# v1_0_r2.net
KiCad netlist of a schematic drawn in EAGLE
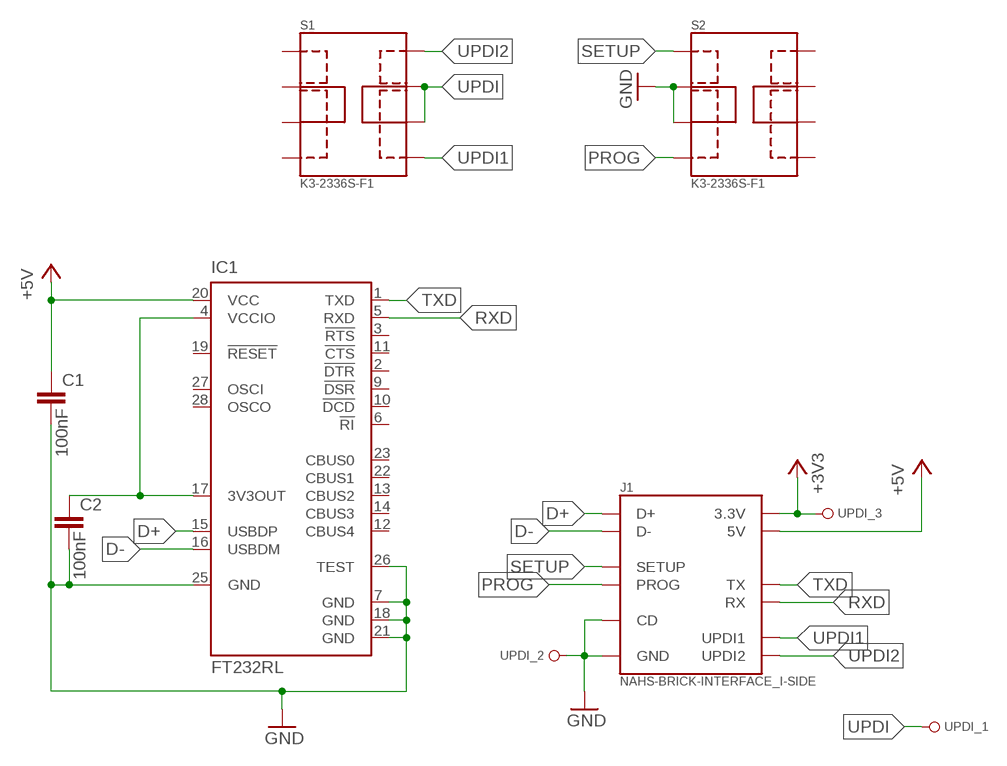
[diagram p0: schematic, sheet 1]

(export (version "E")
  (design (tool "Eeschema 10.0.6"))
  (components
    (comp (ref "C1")
      (value "100nF")
      (footprint "eagle-import:C0805")
      (libsource (lib "eagle-import") (part "C-EUC0805"))
    )
    (comp (ref "C2")
      (value "100nF")
      (footprint "eagle-import:C0805")
      (libsource (lib "eagle-import") (part "C-EUC0805"))
    )
    (comp (ref "IC1")
      (value "FT232RL")
      (footprint "eagle-import:SSOP28")
      (libsource (lib "eagle-import") (part "FT232RL"))
    )
    (comp (ref "J1")
      (value "NAHS-BRICK-INTERFACE_I-SIDE")
      (footprint "eagle-import:54102-0164")
      (libsource (lib "eagle-import") (part "NAHS-BRICK-INTERFACE_I-SIDE"))
    )
    (comp (ref "S1")
      (value "K3-2336S-F1")
      (footprint "eagle-import:K3-2336S-F1")
      (libsource (lib "eagle-import") (part "K3-2336S-F1"))
    )
    (comp (ref "S2")
      (value "K3-2336S-F1")
      (footprint "eagle-import:K3-2336S-F1")
      (libsource (lib "eagle-import") (part "K3-2336S-F1"))
    )
    (comp (ref "UPDI")
      (value "PINHD_1X03_R_1")
      (footprint "eagle-import:1X03_R_1")
      (libsource (lib "eagle-import") (part "PINHD_1X03_R_1"))
    )
  )
  (nets
    (net (code "1") (name "+3V3") (class "Default")
      (node (ref "J1") (pin "16") (pinfunction "3.3V_16") (pintype "bidirectional"))
      (node (ref "UPDI") (pin "3") (pinfunction "1_3") (pintype "bidirectional"))
    )
    (net (code "2") (name "+5V") (class "Default")
      (node (ref "C1") (pin "1") (pinfunction "1_1") (pintype "passive"))
      (node (ref "IC1") (pin "20") (pinfunction "VCC_20") (pintype "power_in"))
      (node (ref "J1") (pin "5") (pinfunction "5V_5") (pintype "bidirectional"))
      (node (ref "J1") (pin "6") (pinfunction "5V_6") (pintype "bidirectional"))
    )
    (net (code "3") (name "D+") (class "Default")
      (node (ref "IC1") (pin "15") (pinfunction "USBDP_15") (pintype "bidirectional"))
      (node (ref "J1") (pin "9") (pinfunction "D+_9") (pintype "bidirectional"))
    )
    (net (code "4") (name "D-") (class "Default")
      (node (ref "IC1") (pin "16") (pinfunction "USBDM_16") (pintype "bidirectional"))
      (node (ref "J1") (pin "10") (pinfunction "D-_10") (pintype "bidirectional"))
    )
    (net (code "5") (name "GND") (class "Default")
      (node (ref "C1") (pin "2") (pinfunction "2_2") (pintype "passive"))
      (node (ref "C2") (pin "2") (pinfunction "2_2") (pintype "passive"))
      (node (ref "IC1") (pin "18") (pinfunction "GND_18") (pintype "power_in"))
      (node (ref "IC1") (pin "21") (pinfunction "GND_21") (pintype "power_in"))
      (node (ref "IC1") (pin "25") (pinfunction "GND_25") (pintype "power_in"))
      (node (ref "IC1") (pin "26") (pinfunction "TEST_26") (pintype "input"))
      (node (ref "IC1") (pin "7") (pinfunction "GND_7") (pintype "power_in"))
      (node (ref "J1") (pin "11") (pinfunction "GND_11") (pintype "bidirectional"))
      (node (ref "J1") (pin "12") (pinfunction "GND_12") (pintype "bidirectional"))
      (node (ref "J1") (pin "13") (pinfunction "CD_13") (pintype "bidirectional"))
      (node (ref "S2") (pin "1.2") (pinfunction "1.2_1.2") (pintype "bidirectional"))
      (node (ref "S2") (pin "1.3") (pinfunction "1.3_1.3") (pintype "bidirectional"))
      (node (ref "UPDI") (pin "2") (pinfunction "1_2") (pintype "bidirectional"))
    )
    (net (code "6") (name "Net-(IC1-3V3OUT)") (class "Default")
      (node (ref "C2") (pin "1") (pinfunction "1_1") (pintype "passive"))
      (node (ref "IC1") (pin "17") (pinfunction "3V3OUT_17") (pintype "output"))
      (node (ref "IC1") (pin "4") (pinfunction "VCCIO_4") (pintype "power_in"))
    )
    (net (code "7") (name "PROG") (class "Default")
      (node (ref "J1") (pin "1") (pinfunction "PROG_1") (pintype "bidirectional"))
      (node (ref "S2") (pin "1.4") (pinfunction "1.4_1.4") (pintype "bidirectional"))
    )
    (net (code "8") (name "RXD") (class "Default")
      (node (ref "IC1") (pin "5") (pinfunction "RXD_5") (pintype "input"))
      (node (ref "J1") (pin "8") (pinfunction "RX_8") (pintype "bidirectional"))
    )
    (net (code "9") (name "SETUP") (class "Default")
      (node (ref "J1") (pin "2") (pinfunction "SETUP_2") (pintype "bidirectional"))
      (node (ref "S2") (pin "1.1") (pinfunction "1.1_1.1") (pintype "bidirectional"))
    )
    (net (code "10") (name "TXD") (class "Default")
      (node (ref "IC1") (pin "1") (pinfunction "TXD_1") (pintype "output"))
      (node (ref "J1") (pin "7") (pinfunction "TX_7") (pintype "bidirectional"))
    )
    (net (code "11") (name "UPDI") (class "Default")
      (node (ref "S1") (pin "2.2") (pinfunction "2.2_2.2") (pintype "bidirectional"))
      (node (ref "S1") (pin "2.3") (pinfunction "2.3_2.3") (pintype "bidirectional"))
      (node (ref "UPDI") (pin "1") (pinfunction "1_1") (pintype "bidirectional"))
    )
    (net (code "12") (name "UPDI1") (class "Default")
      (node (ref "J1") (pin "15") (pinfunction "UPDI1_15") (pintype "bidirectional"))
      (node (ref "S1") (pin "2.4") (pinfunction "2.4_2.4") (pintype "bidirectional"))
    )
    (net (code "13") (name "UPDI2") (class "Default")
      (node (ref "J1") (pin "14") (pinfunction "UPDI2_14") (pintype "bidirectional"))
      (node (ref "S1") (pin "2.1") (pinfunction "2.1_2.1") (pintype "bidirectional"))
    )
    (net (code "14") (name "unconnected-(IC1-CBUS0-Pad23)") (class "Default")
      (node (ref "IC1") (pin "23") (pinfunction "CBUS0_23") (pintype "bidirectional"))
    )
    (net (code "15") (name "unconnected-(IC1-CBUS1-Pad22)") (class "Default")
      (node (ref "IC1") (pin "22") (pinfunction "CBUS1_22") (pintype "bidirectional"))
    )
    (net (code "16") (name "unconnected-(IC1-CBUS2-Pad13)") (class "Default")
      (node (ref "IC1") (pin "13") (pinfunction "CBUS2_13") (pintype "bidirectional"))
    )
    (net (code "17") (name "unconnected-(IC1-CBUS3-Pad14)") (class "Default")
      (node (ref "IC1") (pin "14") (pinfunction "CBUS3_14") (pintype "bidirectional"))
    )
    (net (code "18") (name "unconnected-(IC1-CBUS4-Pad12)") (class "Default")
      (node (ref "IC1") (pin "12") (pinfunction "CBUS4_12") (pintype "bidirectional"))
    )
    (net (code "19") (name "unconnected-(IC1-OSCI-Pad27)") (class "Default")
      (node (ref "IC1") (pin "27") (pinfunction "OSCI_27") (pintype "input"))
    )
    (net (code "20") (name "unconnected-(IC1-OSCO-Pad28)") (class "Default")
      (node (ref "IC1") (pin "28") (pinfunction "OSCO_28") (pintype "output"))
    )
    (net (code "21") (name "unconnected-(IC1-~{CTS}-Pad11)") (class "Default")
      (node (ref "IC1") (pin "11") (pinfunction "~{CTS}_11") (pintype "input"))
    )
    (net (code "22") (name "unconnected-(IC1-~{DCD}-Pad10)") (class "Default")
      (node (ref "IC1") (pin "10") (pinfunction "~{DCD}_10") (pintype "input"))
    )
    (net (code "23") (name "unconnected-(IC1-~{DSR}-Pad9)") (class "Default")
      (node (ref "IC1") (pin "9") (pinfunction "~{DSR}_9") (pintype "input"))
    )
    (net (code "24") (name "unconnected-(IC1-~{DTR}-Pad2)") (class "Default")
      (node (ref "IC1") (pin "2") (pinfunction "~{DTR}_2") (pintype "output"))
    )
    (net (code "25") (name "unconnected-(IC1-~{RESET}-Pad19)") (class "Default")
      (node (ref "IC1") (pin "19") (pinfunction "~{RESET}_19") (pintype "input"))
    )
    (net (code "26") (name "unconnected-(IC1-~{RI}-Pad6)") (class "Default")
      (node (ref "IC1") (pin "6") (pinfunction "~{RI}_6") (pintype "input"))
    )
    (net (code "27") (name "unconnected-(IC1-~{RTS}-Pad3)") (class "Default")
      (node (ref "IC1") (pin "3") (pinfunction "~{RTS}_3") (pintype "output"))
    )
    (net (code "28") (name "unconnected-(S1-Pad1.1)") (class "Default")
      (node (ref "S1") (pin "1.1") (pinfunction "1.1_1.1") (pintype "bidirectional"))
    )
    (net (code "29") (name "unconnected-(S1-Pad1.2)") (class "Default")
      (node (ref "S1") (pin "1.2") (pinfunction "1.2_1.2") (pintype "bidirectional"))
    )
    (net (code "30") (name "unconnected-(S1-Pad1.3)") (class "Default")
      (node (ref "S1") (pin "1.3") (pinfunction "1.3_1.3") (pintype "bidirectional"))
    )
    (net (code "31") (name "unconnected-(S1-Pad1.4)") (class "Default")
      (node (ref "S1") (pin "1.4") (pinfunction "1.4_1.4") (pintype "bidirectional"))
    )
    (net (code "32") (name "unconnected-(S2-Pad2.1)") (class "Default")
      (node (ref "S2") (pin "2.1") (pinfunction "2.1_2.1") (pintype "bidirectional"))
    )
    (net (code "33") (name "unconnected-(S2-Pad2.2)") (class "Default")
      (node (ref "S2") (pin "2.2") (pinfunction "2.2_2.2") (pintype "bidirectional"))
    )
    (net (code "34") (name "unconnected-(S2-Pad2.3)") (class "Default")
      (node (ref "S2") (pin "2.3") (pinfunction "2.3_2.3") (pintype "bidirectional"))
    )
    (net (code "35") (name "unconnected-(S2-Pad2.4)") (class "Default")
      (node (ref "S2") (pin "2.4") (pinfunction "2.4_2.4") (pintype "bidirectional"))
    )
  )
)
